# MCU_board_ATmega328p_v3_0_SN_RevB_LARGE.net
KiCad netlist of a schematic drawn in EAGLE
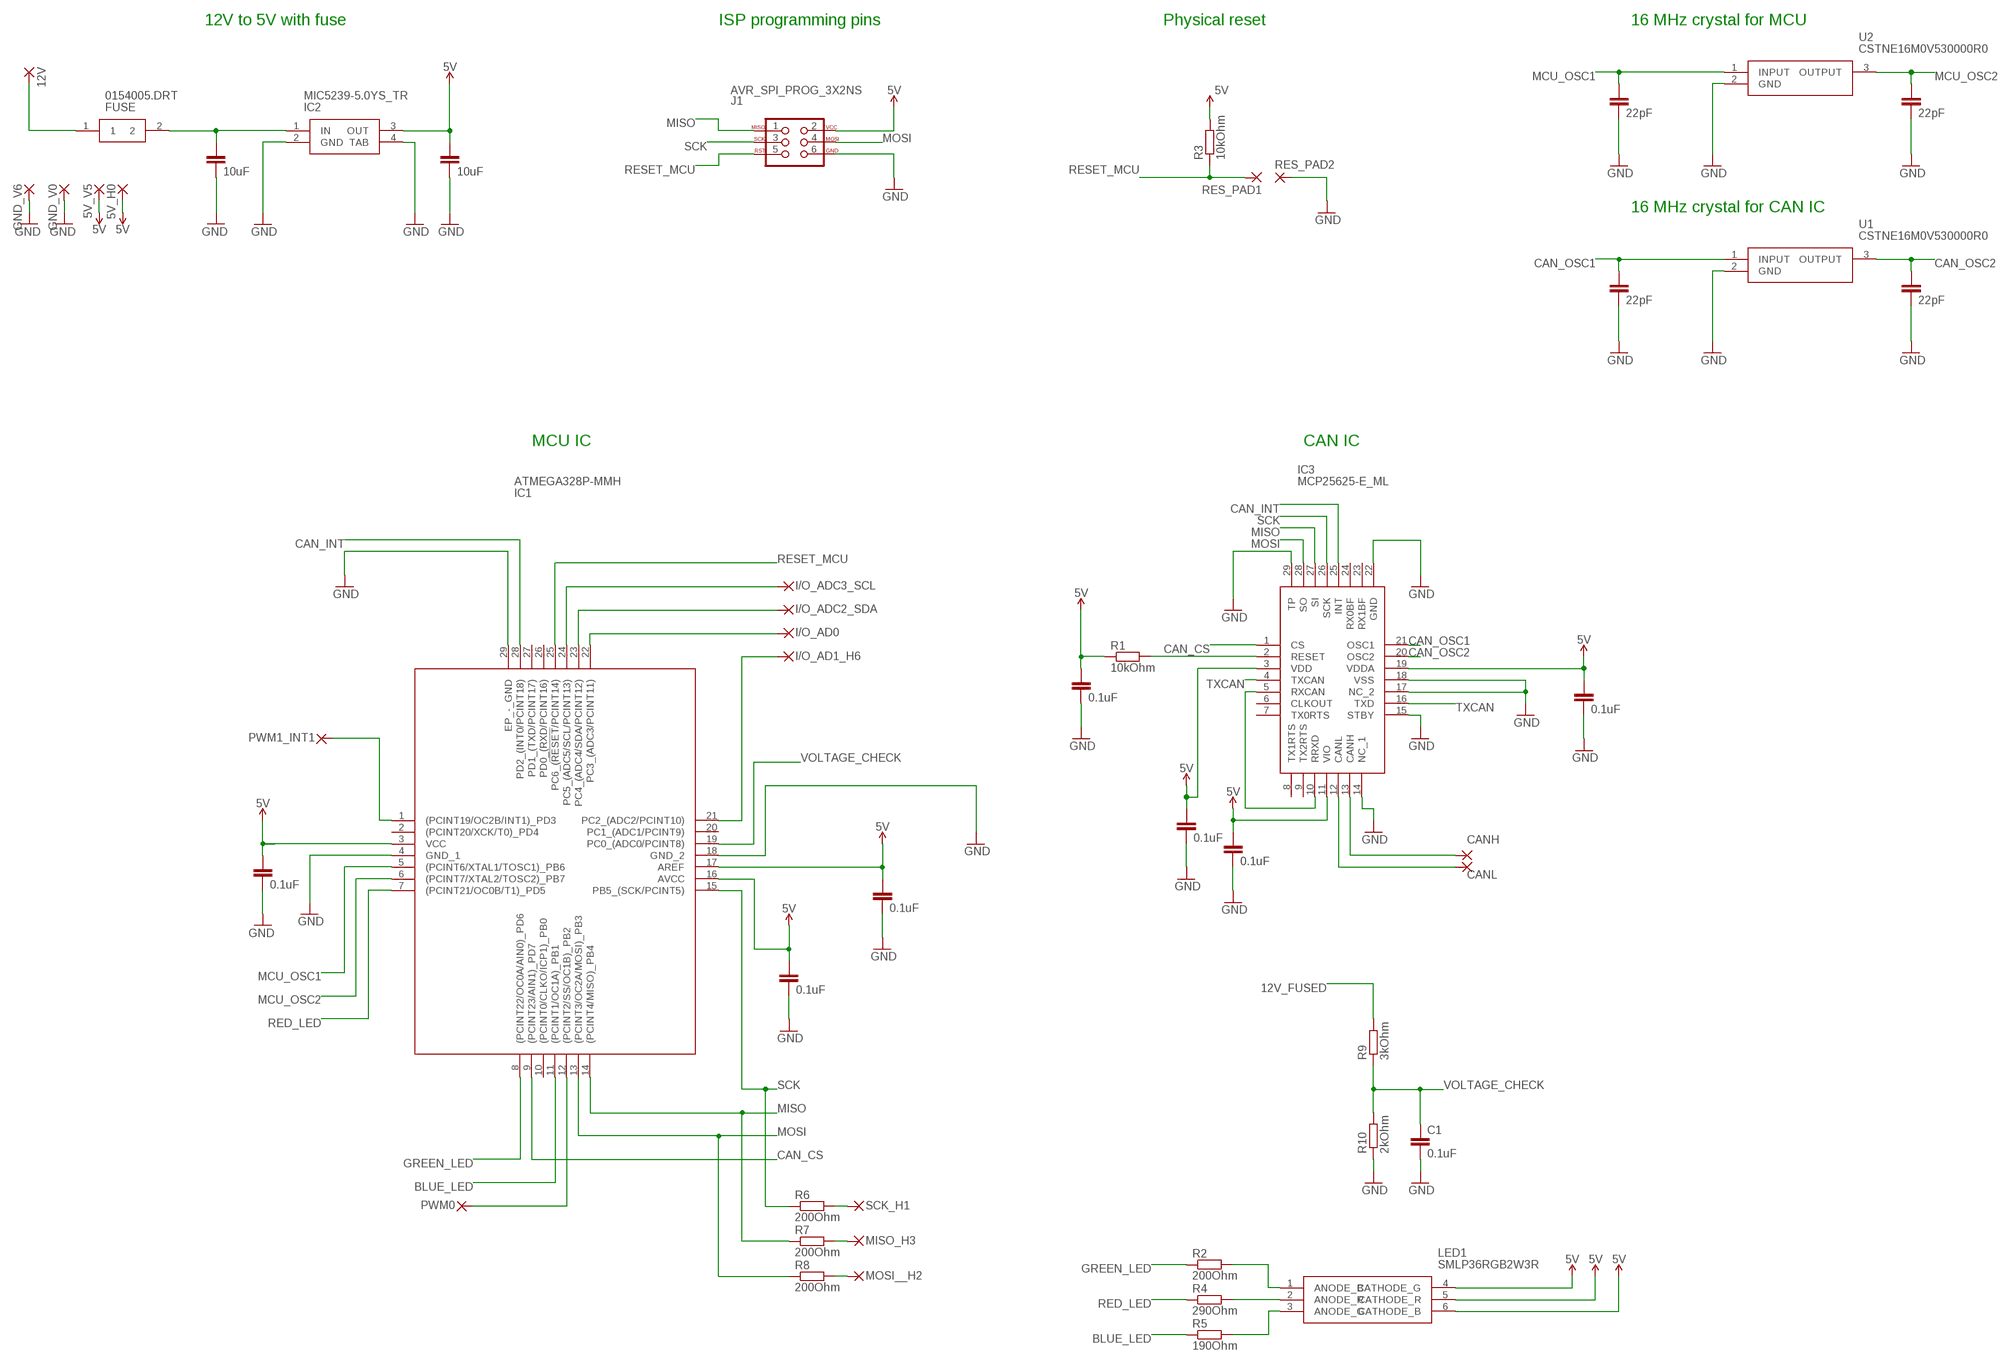
[diagram p0: schematic, sheet 1]

(export (version "E")
  (design (tool "Eeschema 10.0.6"))
  (components
    (comp (ref "5V")
      (value "5V_V5")
      (footprint "eagle-import:2,15_1,0")
      (libsource (lib "eagle-import") (part "2,15/1,0"))
    )
    (comp (ref "5V1")
      (value "5V_H0")
      (footprint "eagle-import:2,15_1,0")
      (libsource (lib "eagle-import") (part "2,15/1,0"))
    )
    (comp (ref "12V")
      (value "12V_V7")
      (footprint "eagle-import:2,15_1,0")
      (libsource (lib "eagle-import") (part "2,15/1,0"))
    )
    (comp (ref "C1")
      (value "0.1uF")
      (footprint "eagle-import:C0603")
      (libsource (lib "eagle-import") (part "CC0603"))
    )
    (comp (ref "C2")
      (value "22pF")
      (footprint "eagle-import:C0603")
      (libsource (lib "eagle-import") (part "CC0603"))
    )
    (comp (ref "C3")
      (value "22pF")
      (footprint "eagle-import:C0603")
      (libsource (lib "eagle-import") (part "CC0603"))
    )
    (comp (ref "C5")
      (value "22pF")
      (footprint "eagle-import:C0603")
      (libsource (lib "eagle-import") (part "CC0603"))
    )
    (comp (ref "C6")
      (value "0.1uF")
      (footprint "eagle-import:C0603")
      (libsource (lib "eagle-import") (part "CC0603"))
    )
    (comp (ref "C7")
      (value "0.1uF")
      (footprint "eagle-import:C0603")
      (libsource (lib "eagle-import") (part "CC0603"))
    )
    (comp (ref "C8")
      (value "0.1uF")
      (footprint "eagle-import:C0603")
      (libsource (lib "eagle-import") (part "CC0603"))
    )
    (comp (ref "C9")
      (value "22pF")
      (footprint "eagle-import:C0603")
      (libsource (lib "eagle-import") (part "CC0603"))
    )
    (comp (ref "C10")
      (value "10uF")
      (footprint "eagle-import:C0603")
      (libsource (lib "eagle-import") (part "CC0603"))
    )
    (comp (ref "C11")
      (value "10uF")
      (footprint "eagle-import:C0603")
      (libsource (lib "eagle-import") (part "CC0603"))
    )
    (comp (ref "C12")
      (value "0.1uF")
      (footprint "eagle-import:C0603")
      (libsource (lib "eagle-import") (part "CC0603"))
    )
    (comp (ref "C13")
      (value "0.1uF")
      (footprint "eagle-import:C0603")
      (libsource (lib "eagle-import") (part "CC0603"))
    )
    (comp (ref "C16")
      (value "0.1uF")
      (footprint "eagle-import:C0603")
      (libsource (lib "eagle-import") (part "CC0603"))
    )
    (comp (ref "C17")
      (value "0.1uF")
      (footprint "eagle-import:C0603")
      (libsource (lib "eagle-import") (part "CC0603"))
    )
    (comp (ref "CANH")
      (value "I/O_CANH_V3")
      (footprint "eagle-import:2,15_1,0")
      (libsource (lib "eagle-import") (part "2,15/1,0"))
    )
    (comp (ref "CANL")
      (value "I/O_CANH_V4")
      (footprint "eagle-import:2,15_1,0")
      (libsource (lib "eagle-import") (part "2,15/1,0"))
    )
    (comp (ref "FUSE")
      (value "0154005.DRT")
      (footprint "eagle-import:0154001.DRT")
      (fields (field (name "RS_PART_NUMBER") "2196260P"))
      (libsource (lib "eagle-import") (part "0154005.DRT"))
    )
    (comp (ref "GND")
      (value "GND_V6")
      (footprint "eagle-import:2,15_1,0")
      (libsource (lib "eagle-import") (part "2,15/1,0"))
    )
    (comp (ref "GND30")
      (value "GND_V0")
      (footprint "eagle-import:2,15_1,0")
      (libsource (lib "eagle-import") (part "2,15/1,0"))
    )
    (comp (ref "I/O_AD0")
      (value "I/O_AD0_H7")
      (footprint "eagle-import:2,15_1,0")
      (libsource (lib "eagle-import") (part "2,15/1,0"))
    )
    (comp (ref "I/O_AD1")
      (value "I/O_AD1_H6")
      (footprint "eagle-import:2,15_1,0")
      (libsource (lib "eagle-import") (part "2,15/1,0"))
    )
    (comp (ref "I/O_ADC2_SDA")
      (value "I/O_ADC2_SDA_H5")
      (footprint "eagle-import:2,15_1,0")
      (libsource (lib "eagle-import") (part "2,15/1,0"))
    )
    (comp (ref "I/O_ADC3_SCL")
      (value "I/O_ADC3_SCL_H4")
      (footprint "eagle-import:2,15_1,0")
      (libsource (lib "eagle-import") (part "2,15/1,0"))
    )
    (comp (ref "IC1")
      (value "ATMEGA328P-MMH")
      (footprint "eagle-import:QFN45P400X400X100-29N")
      (fields (field (name "RS_PART_NUMBER") "1310272P"))
      (libsource (lib "eagle-import") (part "ATMEGA328P-MMH"))
    )
    (comp (ref "IC2")
      (value "MIC5239-5.0YS_TR")
      (footprint "eagle-import:SOT230P700X170-4N")
      (fields
        (field (name "ARROW_PART_NUMBER") "MIC5239-5.0YS TR")
        (field (name "RS_PART_NUMBER") "7275535P")
      )
      (libsource (lib "eagle-import") (part "MIC5239-5.0YS_TR"))
    )
    (comp (ref "IC3")
      (value "MCP25625-E_ML")
      (footprint "eagle-import:QFN65P600X600X100-29N")
      (fields (field (name "ARROW_PART_NUMBER") "MCP25625-E/ML") (field (name "RS_PART_NUMBER") "1654104"))
      (libsource (lib "eagle-import") (part "MCP25625-E_ML"))
    )
    (comp (ref "J1")
      (value "AVR_SPI_PROG_3X2NS")
      (footprint "eagle-import:2X3-NS")
      (libsource (lib "eagle-import") (part "AVR_SPI_PROG_3X2NS"))
    )
    (comp (ref "LED1")
      (value "SMLP36RGB2W3R")
      (footprint "eagle-import:ROHM-1510-(0604)")
      (fields (field (name "RS_PART_NUMBER") "1246884P"))
      (libsource (lib "eagle-import") (part "SMLP36RGB2W3R"))
    )
    (comp (ref "MISO")
      (value "MISO_H3")
      (footprint "eagle-import:2,15_1,0")
      (libsource (lib "eagle-import") (part "2,15/1,0"))
    )
    (comp (ref "MOSI")
      (value "MOSI__H2")
      (footprint "eagle-import:2,15_1,0")
      (libsource (lib "eagle-import") (part "2,15/1,0"))
    )
    (comp (ref "PWM0")
      (value "PWM0_V2")
      (footprint "eagle-import:2,15_1,0")
      (libsource (lib "eagle-import") (part "2,15/1,0"))
    )
    (comp (ref "PWM1_INT1")
      (value "PWM0_INT_V1")
      (footprint "eagle-import:2,15_1,0")
      (libsource (lib "eagle-import") (part "2,15/1,0"))
    )
    (comp (ref "R1")
      (value "10kOhm")
      (footprint "eagle-import:R0603")
      (libsource (lib "eagle-import") (part "RR0603"))
    )
    (comp (ref "R2")
      (value "200Ohm")
      (footprint "eagle-import:R0603")
      (libsource (lib "eagle-import") (part "RR0603"))
    )
    (comp (ref "R3")
      (value "10kOhm")
      (footprint "eagle-import:R0603")
      (libsource (lib "eagle-import") (part "RR0603"))
    )
    (comp (ref "R4")
      (value "290Ohm")
      (footprint "eagle-import:R0603")
      (libsource (lib "eagle-import") (part "RR0603"))
    )
    (comp (ref "R5")
      (value "190Ohm")
      (footprint "eagle-import:R0603")
      (libsource (lib "eagle-import") (part "RR0603"))
    )
    (comp (ref "R6")
      (value "200Ohm")
      (footprint "eagle-import:R0603")
      (libsource (lib "eagle-import") (part "RR0603"))
    )
    (comp (ref "R7")
      (value "200Ohm")
      (footprint "eagle-import:R0603")
      (libsource (lib "eagle-import") (part "RR0603"))
    )
    (comp (ref "R8")
      (value "200Ohm")
      (footprint "eagle-import:R0603")
      (libsource (lib "eagle-import") (part "RR0603"))
    )
    (comp (ref "R9")
      (value "3kOhm")
      (footprint "eagle-import:R0603")
      (libsource (lib "eagle-import") (part "RR0603"))
    )
    (comp (ref "R10")
      (value "2kOhm")
      (footprint "eagle-import:R0603")
      (libsource (lib "eagle-import") (part "RR0603"))
    )
    (comp (ref "RES_PAD1")
      (value "RES_PAD")
      (footprint "eagle-import:SMD1,27-2,54")
      (libsource (lib "eagle-import") (part "SMD2"))
    )
    (comp (ref "RES_PAD2")
      (value "RES_PAD2")
      (footprint "eagle-import:SMD1,27-2,54")
      (libsource (lib "eagle-import") (part "SMD2"))
    )
    (comp (ref "SCK")
      (value "SCK_H1")
      (footprint "eagle-import:2,15_1,0")
      (libsource (lib "eagle-import") (part "2,15/1,0"))
    )
    (comp (ref "U1")
      (value "CSTNE16M0V530000R0")
      (footprint "eagle-import:CSTNE16M0V530000R0")
      (libsource (lib "eagle-import") (part "CSTNE16M0V530000R0"))
    )
    (comp (ref "U2")
      (value "CSTNE16M0V530000R0")
      (footprint "eagle-import:CSTNE16M0V530000R0")
      (libsource (lib "eagle-import") (part "CSTNE16M0V530000R0"))
    )
  )
  (nets
    (net (code "1") (name "/12V_FUSED") (class "Default")
      (node (ref "C10") (pin "1") (pinfunction "1_1") (pintype "passive"))
      (node (ref "FUSE") (pin "2") (pinfunction "2_2") (pintype "bidirectional"))
      (node (ref "IC2") (pin "1") (pinfunction "IN_1") (pintype "bidirectional"))
      (node (ref "R9") (pin "2") (pinfunction "2_2") (pintype "passive"))
    )
    (net (code "2") (name "/BLUE_LED") (class "Default")
      (node (ref "IC1") (pin "11") (pinfunction "(PCINT1/OC1A)_PB1_11") (pintype "bidirectional"))
      (node (ref "R5") (pin "1") (pinfunction "1_1") (pintype "passive"))
    )
    (net (code "3") (name "/CANH") (class "Default")
      (node (ref "CANH") (pin "1") (pinfunction "P_1") (pintype "passive"))
      (node (ref "IC3") (pin "13") (pinfunction "CANH_13") (pintype "bidirectional"))
    )
    (net (code "4") (name "/CANL") (class "Default")
      (node (ref "CANL") (pin "1") (pinfunction "P_1") (pintype "passive"))
      (node (ref "IC3") (pin "12") (pinfunction "CANL_12") (pintype "bidirectional"))
    )
    (net (code "5") (name "/CAN_CS") (class "Default")
      (node (ref "IC1") (pin "9") (pinfunction "(PCINT23/AIN1)_PD7_9") (pintype "bidirectional"))
      (node (ref "IC3") (pin "1") (pinfunction "CS_1") (pintype "input"))
    )
    (net (code "6") (name "/CAN_INT") (class "Default")
      (node (ref "IC1") (pin "28") (pinfunction "PD2_(INT0/PCINT18)_28") (pintype "bidirectional"))
      (node (ref "IC3") (pin "25") (pinfunction "INT_25") (pintype "input"))
    )
    (net (code "7") (name "/CAN_OSC1") (class "Default")
      (node (ref "C5") (pin "1") (pinfunction "1_1") (pintype "passive"))
      (node (ref "IC3") (pin "21") (pinfunction "OSC1_21") (pintype "bidirectional"))
      (node (ref "U1") (pin "1") (pinfunction "INPUT_1") (pintype "bidirectional"))
    )
    (net (code "8") (name "/CAN_OSC2") (class "Default")
      (node (ref "C2") (pin "1") (pinfunction "1_1") (pintype "passive"))
      (node (ref "IC3") (pin "20") (pinfunction "OSC2_20") (pintype "bidirectional"))
      (node (ref "U1") (pin "3") (pinfunction "OUTPUT_3") (pintype "bidirectional"))
    )
    (net (code "9") (name "/GREEN_LED") (class "Default")
      (node (ref "IC1") (pin "8") (pinfunction "(PCINT22/OC0A/AIN0)_PD6_8") (pintype "bidirectional"))
      (node (ref "R2") (pin "1") (pinfunction "1_1") (pintype "passive"))
    )
    (net (code "10") (name "/MCU_OSC1") (class "Default")
      (node (ref "C3") (pin "1") (pinfunction "1_1") (pintype "passive"))
      (node (ref "IC1") (pin "5") (pinfunction "(PCINT6/XTAL1/TOSC1)_PB6_5") (pintype "bidirectional"))
      (node (ref "U2") (pin "1") (pinfunction "INPUT_1") (pintype "bidirectional"))
    )
    (net (code "11") (name "/MCU_OSC2") (class "Default")
      (node (ref "C9") (pin "1") (pinfunction "1_1") (pintype "passive"))
      (node (ref "IC1") (pin "6") (pinfunction "(PCINT7/XTAL2/TOSC2)_PB7_6") (pintype "bidirectional"))
      (node (ref "U2") (pin "3") (pinfunction "OUTPUT_3") (pintype "bidirectional"))
    )
    (net (code "12") (name "/MISO") (class "Default")
      (node (ref "IC1") (pin "14") (pinfunction "(PCINT4/MISO)_PB4_14") (pintype "bidirectional"))
      (node (ref "IC3") (pin "27") (pinfunction "SI_27") (pintype "bidirectional"))
      (node (ref "J1") (pin "1") (pinfunction "1_1") (pintype "passive"))
      (node (ref "R7") (pin "1") (pinfunction "1_1") (pintype "passive"))
    )
    (net (code "13") (name "/MOSI") (class "Default")
      (node (ref "IC1") (pin "13") (pinfunction "(PCINT3/OC2A/MOSI)_PB3_13") (pintype "bidirectional"))
      (node (ref "IC3") (pin "28") (pinfunction "SO_28") (pintype "bidirectional"))
      (node (ref "J1") (pin "4") (pinfunction "4_4") (pintype "passive"))
      (node (ref "R8") (pin "1") (pinfunction "1_1") (pintype "passive"))
    )
    (net (code "14") (name "/RED_LED") (class "Default")
      (node (ref "IC1") (pin "7") (pinfunction "(PCINT21/OC0B/T1)_PD5_7") (pintype "bidirectional"))
      (node (ref "R4") (pin "1") (pinfunction "1_1") (pintype "passive"))
    )
    (net (code "15") (name "/RESET_MCU") (class "Default")
      (node (ref "IC1") (pin "25") (pinfunction "PC6_(~{RESET}/PCINT14)_25") (pintype "bidirectional"))
      (node (ref "J1") (pin "5") (pinfunction "5_5") (pintype "passive"))
      (node (ref "R3") (pin "1") (pinfunction "1_1") (pintype "passive"))
      (node (ref "RES_PAD1") (pin "1") (pinfunction "P_1") (pintype "passive"))
    )
    (net (code "16") (name "/SCK") (class "Default")
      (node (ref "IC1") (pin "15") (pinfunction "PB5_(SCK/PCINT5)_15") (pintype "bidirectional"))
      (node (ref "IC3") (pin "26") (pinfunction "SCK_26") (pintype "bidirectional"))
      (node (ref "J1") (pin "3") (pinfunction "3_3") (pintype "passive"))
      (node (ref "R6") (pin "1") (pinfunction "1_1") (pintype "passive"))
    )
    (net (code "17") (name "/TXCAN") (class "Default")
      (node (ref "IC3") (pin "16") (pinfunction "TXD_16") (pintype "bidirectional"))
      (node (ref "IC3") (pin "4") (pinfunction "TXCAN_4") (pintype "bidirectional"))
    )
    (net (code "18") (name "/VOLTAGE_CHECK") (class "Default")
      (node (ref "C1") (pin "1") (pinfunction "1_1") (pintype "passive"))
      (node (ref "IC1") (pin "19") (pinfunction "PC0_(ADC0/PCINT8)_19") (pintype "bidirectional"))
      (node (ref "R10") (pin "2") (pinfunction "2_2") (pintype "passive"))
      (node (ref "R9") (pin "1") (pinfunction "1_1") (pintype "passive"))
    )
    (net (code "19") (name "5V") (class "Default")
      (node (ref "5V") (pin "1") (pinfunction "P_1") (pintype "passive"))
      (node (ref "5V1") (pin "1") (pinfunction "P_1") (pintype "passive"))
      (node (ref "C11") (pin "1") (pinfunction "1_1") (pintype "passive"))
      (node (ref "C12") (pin "1") (pinfunction "1_1") (pintype "passive"))
      (node (ref "C13") (pin "1") (pinfunction "1_1") (pintype "passive"))
      (node (ref "C16") (pin "1") (pinfunction "1_1") (pintype "passive"))
      (node (ref "C17") (pin "1") (pinfunction "1_1") (pintype "passive"))
      (node (ref "C6") (pin "1") (pinfunction "1_1") (pintype "passive"))
      (node (ref "C7") (pin "1") (pinfunction "1_1") (pintype "passive"))
      (node (ref "C8") (pin "1") (pinfunction "1_1") (pintype "passive"))
      (node (ref "IC1") (pin "16") (pinfunction "AVCC_16") (pintype "bidirectional"))
      (node (ref "IC1") (pin "17") (pinfunction "AREF_17") (pintype "bidirectional"))
      (node (ref "IC1") (pin "3") (pinfunction "VCC_3") (pintype "bidirectional"))
      (node (ref "IC2") (pin "3") (pinfunction "OUT_3") (pintype "bidirectional"))
      (node (ref "IC3") (pin "11") (pinfunction "VIO_11") (pintype "bidirectional"))
      (node (ref "IC3") (pin "19") (pinfunction "VDDA_19") (pintype "power_in"))
      (node (ref "IC3") (pin "3") (pinfunction "VDD_3") (pintype "power_in"))
      (node (ref "J1") (pin "2") (pinfunction "2_2") (pintype "passive"))
      (node (ref "LED1") (pin "4") (pinfunction "CATHODE_G_4") (pintype "bidirectional"))
      (node (ref "LED1") (pin "5") (pinfunction "CATHODE_R_5") (pintype "bidirectional"))
      (node (ref "LED1") (pin "6") (pinfunction "CATHODE_B_6") (pintype "bidirectional"))
      (node (ref "R1") (pin "1") (pinfunction "1_1") (pintype "passive"))
      (node (ref "R3") (pin "2") (pinfunction "2_2") (pintype "passive"))
    )
    (net (code "20") (name "GND") (class "Default")
      (node (ref "C1") (pin "2") (pinfunction "2_2") (pintype "passive"))
      (node (ref "C10") (pin "2") (pinfunction "2_2") (pintype "passive"))
      (node (ref "C11") (pin "2") (pinfunction "2_2") (pintype "passive"))
      (node (ref "C12") (pin "2") (pinfunction "2_2") (pintype "passive"))
      (node (ref "C13") (pin "2") (pinfunction "2_2") (pintype "passive"))
      (node (ref "C16") (pin "2") (pinfunction "2_2") (pintype "passive"))
      (node (ref "C17") (pin "2") (pinfunction "2_2") (pintype "passive"))
      (node (ref "C2") (pin "2") (pinfunction "2_2") (pintype "passive"))
      (node (ref "C3") (pin "2") (pinfunction "2_2") (pintype "passive"))
      (node (ref "C5") (pin "2") (pinfunction "2_2") (pintype "passive"))
      (node (ref "C6") (pin "2") (pinfunction "2_2") (pintype "passive"))
      (node (ref "C7") (pin "2") (pinfunction "2_2") (pintype "passive"))
      (node (ref "C8") (pin "2") (pinfunction "2_2") (pintype "passive"))
      (node (ref "C9") (pin "2") (pinfunction "2_2") (pintype "passive"))
      (node (ref "GND") (pin "1") (pinfunction "P_1") (pintype "passive"))
      (node (ref "GND30") (pin "1") (pinfunction "P_1") (pintype "passive"))
      (node (ref "IC1") (pin "18") (pinfunction "GND_2_18") (pintype "bidirectional"))
      (node (ref "IC1") (pin "29") (pinfunction "EP_-_GND_29") (pintype "bidirectional"))
      (node (ref "IC1") (pin "4") (pinfunction "GND_1_4") (pintype "bidirectional"))
      (node (ref "IC2") (pin "2") (pinfunction "GND_2") (pintype "bidirectional"))
      (node (ref "IC2") (pin "4") (pinfunction "TAB_4") (pintype "bidirectional"))
      (node (ref "IC3") (pin "14") (pinfunction "NC_1_14") (pintype "bidirectional"))
      (node (ref "IC3") (pin "15") (pinfunction "STBY_15") (pintype "bidirectional"))
      (node (ref "IC3") (pin "17") (pinfunction "NC_2_17") (pintype "bidirectional"))
      (node (ref "IC3") (pin "18") (pinfunction "VSS_18") (pintype "power_in"))
      (node (ref "IC3") (pin "22") (pinfunction "GND_22") (pintype "power_in"))
      (node (ref "IC3") (pin "29") (pinfunction "TP_29") (pintype "bidirectional"))
      (node (ref "J1") (pin "6") (pinfunction "6_6") (pintype "passive"))
      (node (ref "R10") (pin "1") (pinfunction "1_1") (pintype "passive"))
      (node (ref "RES_PAD2") (pin "1") (pinfunction "P_1") (pintype "passive"))
      (node (ref "U1") (pin "2") (pinfunction "GND_2") (pintype "bidirectional"))
      (node (ref "U2") (pin "2") (pinfunction "GND_2") (pintype "bidirectional"))
    )
    (net (code "21") (name "Net-(12V-P)") (class "Default")
      (node (ref "12V") (pin "1") (pinfunction "P_1") (pintype "passive"))
      (node (ref "FUSE") (pin "1") (pinfunction "1_1") (pintype "bidirectional"))
    )
    (net (code "22") (name "Net-(I/O_AD0-P)") (class "Default")
      (node (ref "I/O_AD0") (pin "1") (pinfunction "P_1") (pintype "passive"))
      (node (ref "IC1") (pin "22") (pinfunction "PC3_(ADC3/PCINT11)_22") (pintype "bidirectional"))
    )
    (net (code "23") (name "Net-(I/O_AD1-P)") (class "Default")
      (node (ref "I/O_AD1") (pin "1") (pinfunction "P_1") (pintype "passive"))
      (node (ref "IC1") (pin "21") (pinfunction "PC2_(ADC2/PCINT10)_21") (pintype "bidirectional"))
    )
    (net (code "24") (name "Net-(I/O_ADC2_SDA-P)") (class "Default")
      (node (ref "I/O_ADC2_SDA") (pin "1") (pinfunction "P_1") (pintype "passive"))
      (node (ref "IC1") (pin "23") (pinfunction "PC4_(ADC4/SDA/PCINT12)_23") (pintype "bidirectional"))
    )
    (net (code "25") (name "Net-(I/O_ADC3_SCL-P)") (class "Default")
      (node (ref "I/O_ADC3_SCL") (pin "1") (pinfunction "P_1") (pintype "passive"))
      (node (ref "IC1") (pin "24") (pinfunction "PC5_(ADC5/SCL/PCINT13)_24") (pintype "bidirectional"))
    )
    (net (code "26") (name "Net-(IC1-(PCINT2{slash}SS{slash}OC1B)_PB2)") (class "Default")
      (node (ref "IC1") (pin "12") (pinfunction "(PCINT2/SS/OC1B)_PB2_12") (pintype "bidirectional"))
      (node (ref "PWM0") (pin "1") (pinfunction "P_1") (pintype "passive"))
    )
    (net (code "27") (name "Net-(IC1-(PCINT19{slash}OC2B{slash}INT1)_PD3)") (class "Default")
      (node (ref "IC1") (pin "1") (pinfunction "(PCINT19/OC2B/INT1)_PD3_1") (pintype "bidirectional"))
      (node (ref "PWM1_INT1") (pin "1") (pinfunction "P_1") (pintype "passive"))
    )
    (net (code "28") (name "Net-(IC3-RESET)") (class "Default")
      (node (ref "IC3") (pin "2") (pinfunction "RESET_2") (pintype "bidirectional"))
      (node (ref "R1") (pin "2") (pinfunction "2_2") (pintype "passive"))
    )
    (net (code "29") (name "Net-(IC3-RRXD)") (class "Default")
      (node (ref "IC3") (pin "10") (pinfunction "RRXD_10") (pintype "bidirectional"))
      (node (ref "IC3") (pin "5") (pinfunction "RXCAN_5") (pintype "bidirectional"))
    )
    (net (code "30") (name "Net-(LED1-ANODE_B)") (class "Default")
      (node (ref "LED1") (pin "1") (pinfunction "ANODE_B_1") (pintype "bidirectional"))
      (node (ref "R2") (pin "2") (pinfunction "2_2") (pintype "passive"))
    )
    (net (code "31") (name "Net-(LED1-ANODE_G)") (class "Default")
      (node (ref "LED1") (pin "3") (pinfunction "ANODE_G_3") (pintype "bidirectional"))
      (node (ref "R5") (pin "2") (pinfunction "2_2") (pintype "passive"))
    )
    (net (code "32") (name "Net-(LED1-ANODE_R)") (class "Default")
      (node (ref "LED1") (pin "2") (pinfunction "ANODE_R_2") (pintype "bidirectional"))
      (node (ref "R4") (pin "2") (pinfunction "2_2") (pintype "passive"))
    )
    (net (code "33") (name "Net-(MISO-P)") (class "Default")
      (node (ref "MISO") (pin "1") (pinfunction "P_1") (pintype "passive"))
      (node (ref "R7") (pin "2") (pinfunction "2_2") (pintype "passive"))
    )
    (net (code "34") (name "Net-(MOSI-P)") (class "Default")
      (node (ref "MOSI") (pin "1") (pinfunction "P_1") (pintype "passive"))
      (node (ref "R8") (pin "2") (pinfunction "2_2") (pintype "passive"))
    )
    (net (code "35") (name "Net-(SCK-P)") (class "Default")
      (node (ref "R6") (pin "2") (pinfunction "2_2") (pintype "passive"))
      (node (ref "SCK") (pin "1") (pinfunction "P_1") (pintype "passive"))
    )
    (net (code "36") (name "unconnected-(IC1-(PCINT0{slash}CLKO{slash}ICP1)_PB0-Pad10)") (class "Default")
      (node (ref "IC1") (pin "10") (pinfunction "(PCINT0/CLKO/ICP1)_PB0_10") (pintype "bidirectional"))
    )
    (net (code "37") (name "unconnected-(IC1-(PCINT20{slash}XCK{slash}T0)_PD4-Pad2)") (class "Default")
      (node (ref "IC1") (pin "2") (pinfunction "(PCINT20/XCK/T0)_PD4_2") (pintype "bidirectional"))
    )
    (net (code "38") (name "unconnected-(IC1-PC1_(ADC1{slash}PCINT9)-Pad20)") (class "Default")
      (node (ref "IC1") (pin "20") (pinfunction "PC1_(ADC1/PCINT9)_20") (pintype "bidirectional"))
    )
    (net (code "39") (name "unconnected-(IC1-PD0_(RXD{slash}PCINT16)-Pad26)") (class "Default")
      (node (ref "IC1") (pin "26") (pinfunction "PD0_(RXD/PCINT16)_26") (pintype "bidirectional"))
    )
    (net (code "40") (name "unconnected-(IC1-PD1_(TXD{slash}PCINT17)-Pad27)") (class "Default")
      (node (ref "IC1") (pin "27") (pinfunction "PD1_(TXD/PCINT17)_27") (pintype "bidirectional"))
    )
    (net (code "41") (name "unconnected-(IC3-CLKOUT-Pad6)") (class "Default")
      (node (ref "IC3") (pin "6") (pinfunction "CLKOUT_6") (pintype "output"))
    )
    (net (code "42") (name "unconnected-(IC3-RX0BF-Pad24)") (class "Default")
      (node (ref "IC3") (pin "24") (pinfunction "RX0BF_24") (pintype "bidirectional"))
    )
    (net (code "43") (name "unconnected-(IC3-RX1BF-Pad23)") (class "Default")
      (node (ref "IC3") (pin "23") (pinfunction "RX1BF_23") (pintype "bidirectional"))
    )
    (net (code "44") (name "unconnected-(IC3-TX0RTS-Pad7)") (class "Default")
      (node (ref "IC3") (pin "7") (pinfunction "TX0RTS_7") (pintype "bidirectional"))
    )
    (net (code "45") (name "unconnected-(IC3-TX1RTS-Pad8)") (class "Default")
      (node (ref "IC3") (pin "8") (pinfunction "TX1RTS_8") (pintype "bidirectional"))
    )
    (net (code "46") (name "unconnected-(IC3-TX2RTS-Pad9)") (class "Default")
      (node (ref "IC3") (pin "9") (pinfunction "TX2RTS_9") (pintype "bidirectional"))
    )
  )
)
